# li-ion_v2.net
KiCad netlist of a schematic drawn in EAGLE
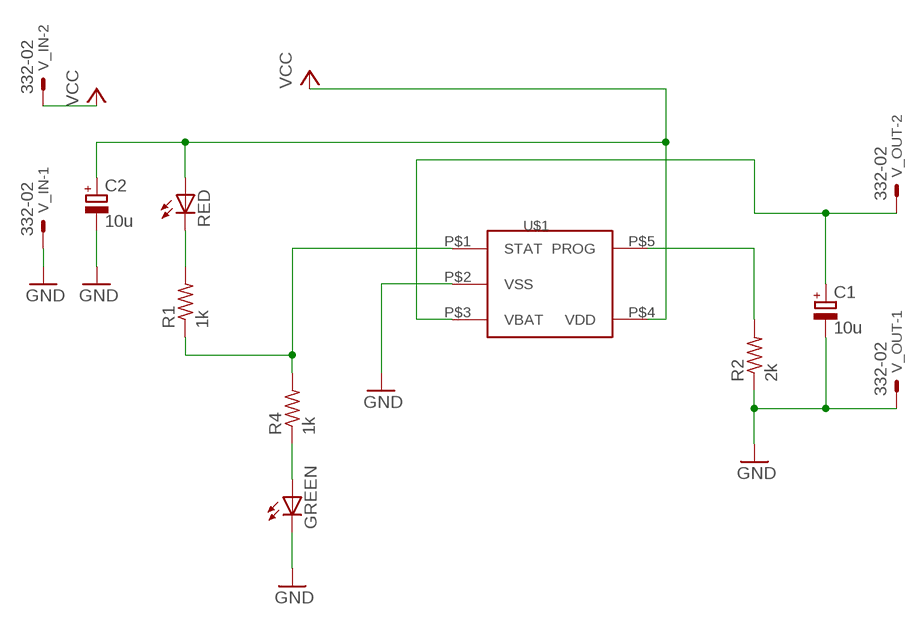
[diagram p0: schematic, sheet 1]

(export (version "E")
  (design (tool "Eeschema 10.0.6"))
  (components
    (comp (ref "C1")
      (value "10u")
      (footprint "eagle-import:E1,8-4")
      (libsource (lib "eagle-import") (part "CPOL-EUE1.8-4"))
    )
    (comp (ref "C2")
      (value "10u")
      (footprint "eagle-import:E1,8-4")
      (libsource (lib "eagle-import") (part "CPOL-EUE1.8-4"))
    )
    (comp (ref "GREEN")
      (value "LED3MM")
      (footprint "eagle-import:LED3MM")
      (libsource (lib "eagle-import") (part "LED3MM"))
    )
    (comp (ref "R1")
      (value "1k")
      (footprint "eagle-import:0204_5")
      (libsource (lib "eagle-import") (part "R-US_0204/5"))
    )
    (comp (ref "R2")
      (value "2k")
      (footprint "eagle-import:0204_5")
      (libsource (lib "eagle-import") (part "R-US_0204/5"))
    )
    (comp (ref "R4")
      (value "1k")
      (footprint "eagle-import:0204_5")
      (libsource (lib "eagle-import") (part "R-US_0204/5"))
    )
    (comp (ref "RED")
      (value "LED3MM")
      (footprint "eagle-import:LED3MM")
      (libsource (lib "eagle-import") (part "LED3MM"))
    )
    (comp (ref "U$1")
      (value "MCP73831")
      (footprint "eagle-import:5PIN_SOT23")
      (libsource (lib "eagle-import") (part "MCP73831"))
    )
    (comp (ref "V_IN")
      (value "332-02")
      (footprint "eagle-import:332-02")
      (libsource (lib "eagle-import") (part "332-02"))
    )
    (comp (ref "V_OUT")
      (value "332-02")
      (footprint "eagle-import:332-02")
      (libsource (lib "eagle-import") (part "332-02"))
    )
  )
  (nets
    (net (code "1") (name "GND") (class "Default")
      (node (ref "C1") (pin "-") (pinfunction "-_-") (pintype "passive"))
      (node (ref "C2") (pin "-") (pinfunction "-_-") (pintype "passive"))
      (node (ref "GREEN") (pin "K") (pinfunction "C_K") (pintype "passive"))
      (node (ref "R2") (pin "1") (pinfunction "1_1") (pintype "passive"))
      (node (ref "U$1") (pin "P$2") (pinfunction "VSS_P$2") (pintype "bidirectional"))
      (node (ref "V_IN") (pin "1") (pinfunction "S_1") (pintype "passive"))
      (node (ref "V_OUT") (pin "1") (pinfunction "S_1") (pintype "passive"))
    )
    (net (code "2") (name "Net-(GREEN-PadA)") (class "Default")
      (node (ref "GREEN") (pin "A") (pinfunction "A_A") (pintype "passive"))
      (node (ref "R4") (pin "1") (pinfunction "1_1") (pintype "passive"))
    )
    (net (code "3") (name "Net-(RED-C)") (class "Default")
      (node (ref "R1") (pin "2") (pinfunction "2_2") (pintype "passive"))
      (node (ref "RED") (pin "K") (pinfunction "C_K") (pintype "passive"))
    )
    (net (code "4") (name "Net-(U$1-PROG)") (class "Default")
      (node (ref "R2") (pin "2") (pinfunction "2_2") (pintype "passive"))
      (node (ref "U$1") (pin "P$5") (pinfunction "PROG_P$5") (pintype "bidirectional"))
    )
    (net (code "5") (name "Net-(U$1-STAT)") (class "Default")
      (node (ref "R1") (pin "1") (pinfunction "1_1") (pintype "passive"))
      (node (ref "R4") (pin "2") (pinfunction "2_2") (pintype "passive"))
      (node (ref "U$1") (pin "P$1") (pinfunction "STAT_P$1") (pintype "bidirectional"))
    )
    (net (code "6") (name "Net-(U$1-VBAT)") (class "Default")
      (node (ref "C1") (pin "+") (pinfunction "+_+") (pintype "passive"))
      (node (ref "U$1") (pin "P$3") (pinfunction "VBAT_P$3") (pintype "bidirectional"))
      (node (ref "V_OUT") (pin "2") (pinfunction "S_2") (pintype "passive"))
    )
    (net (code "7") (name "VCC") (class "Default")
      (node (ref "C2") (pin "+") (pinfunction "+_+") (pintype "passive"))
      (node (ref "RED") (pin "A") (pinfunction "A_A") (pintype "passive"))
      (node (ref "U$1") (pin "P$4") (pinfunction "VDD_P$4") (pintype "bidirectional"))
      (node (ref "V_IN") (pin "2") (pinfunction "S_2") (pintype "passive"))
    )
  )
)
